# 6coils.net
KiCad netlist of a schematic drawn in EasyEDA
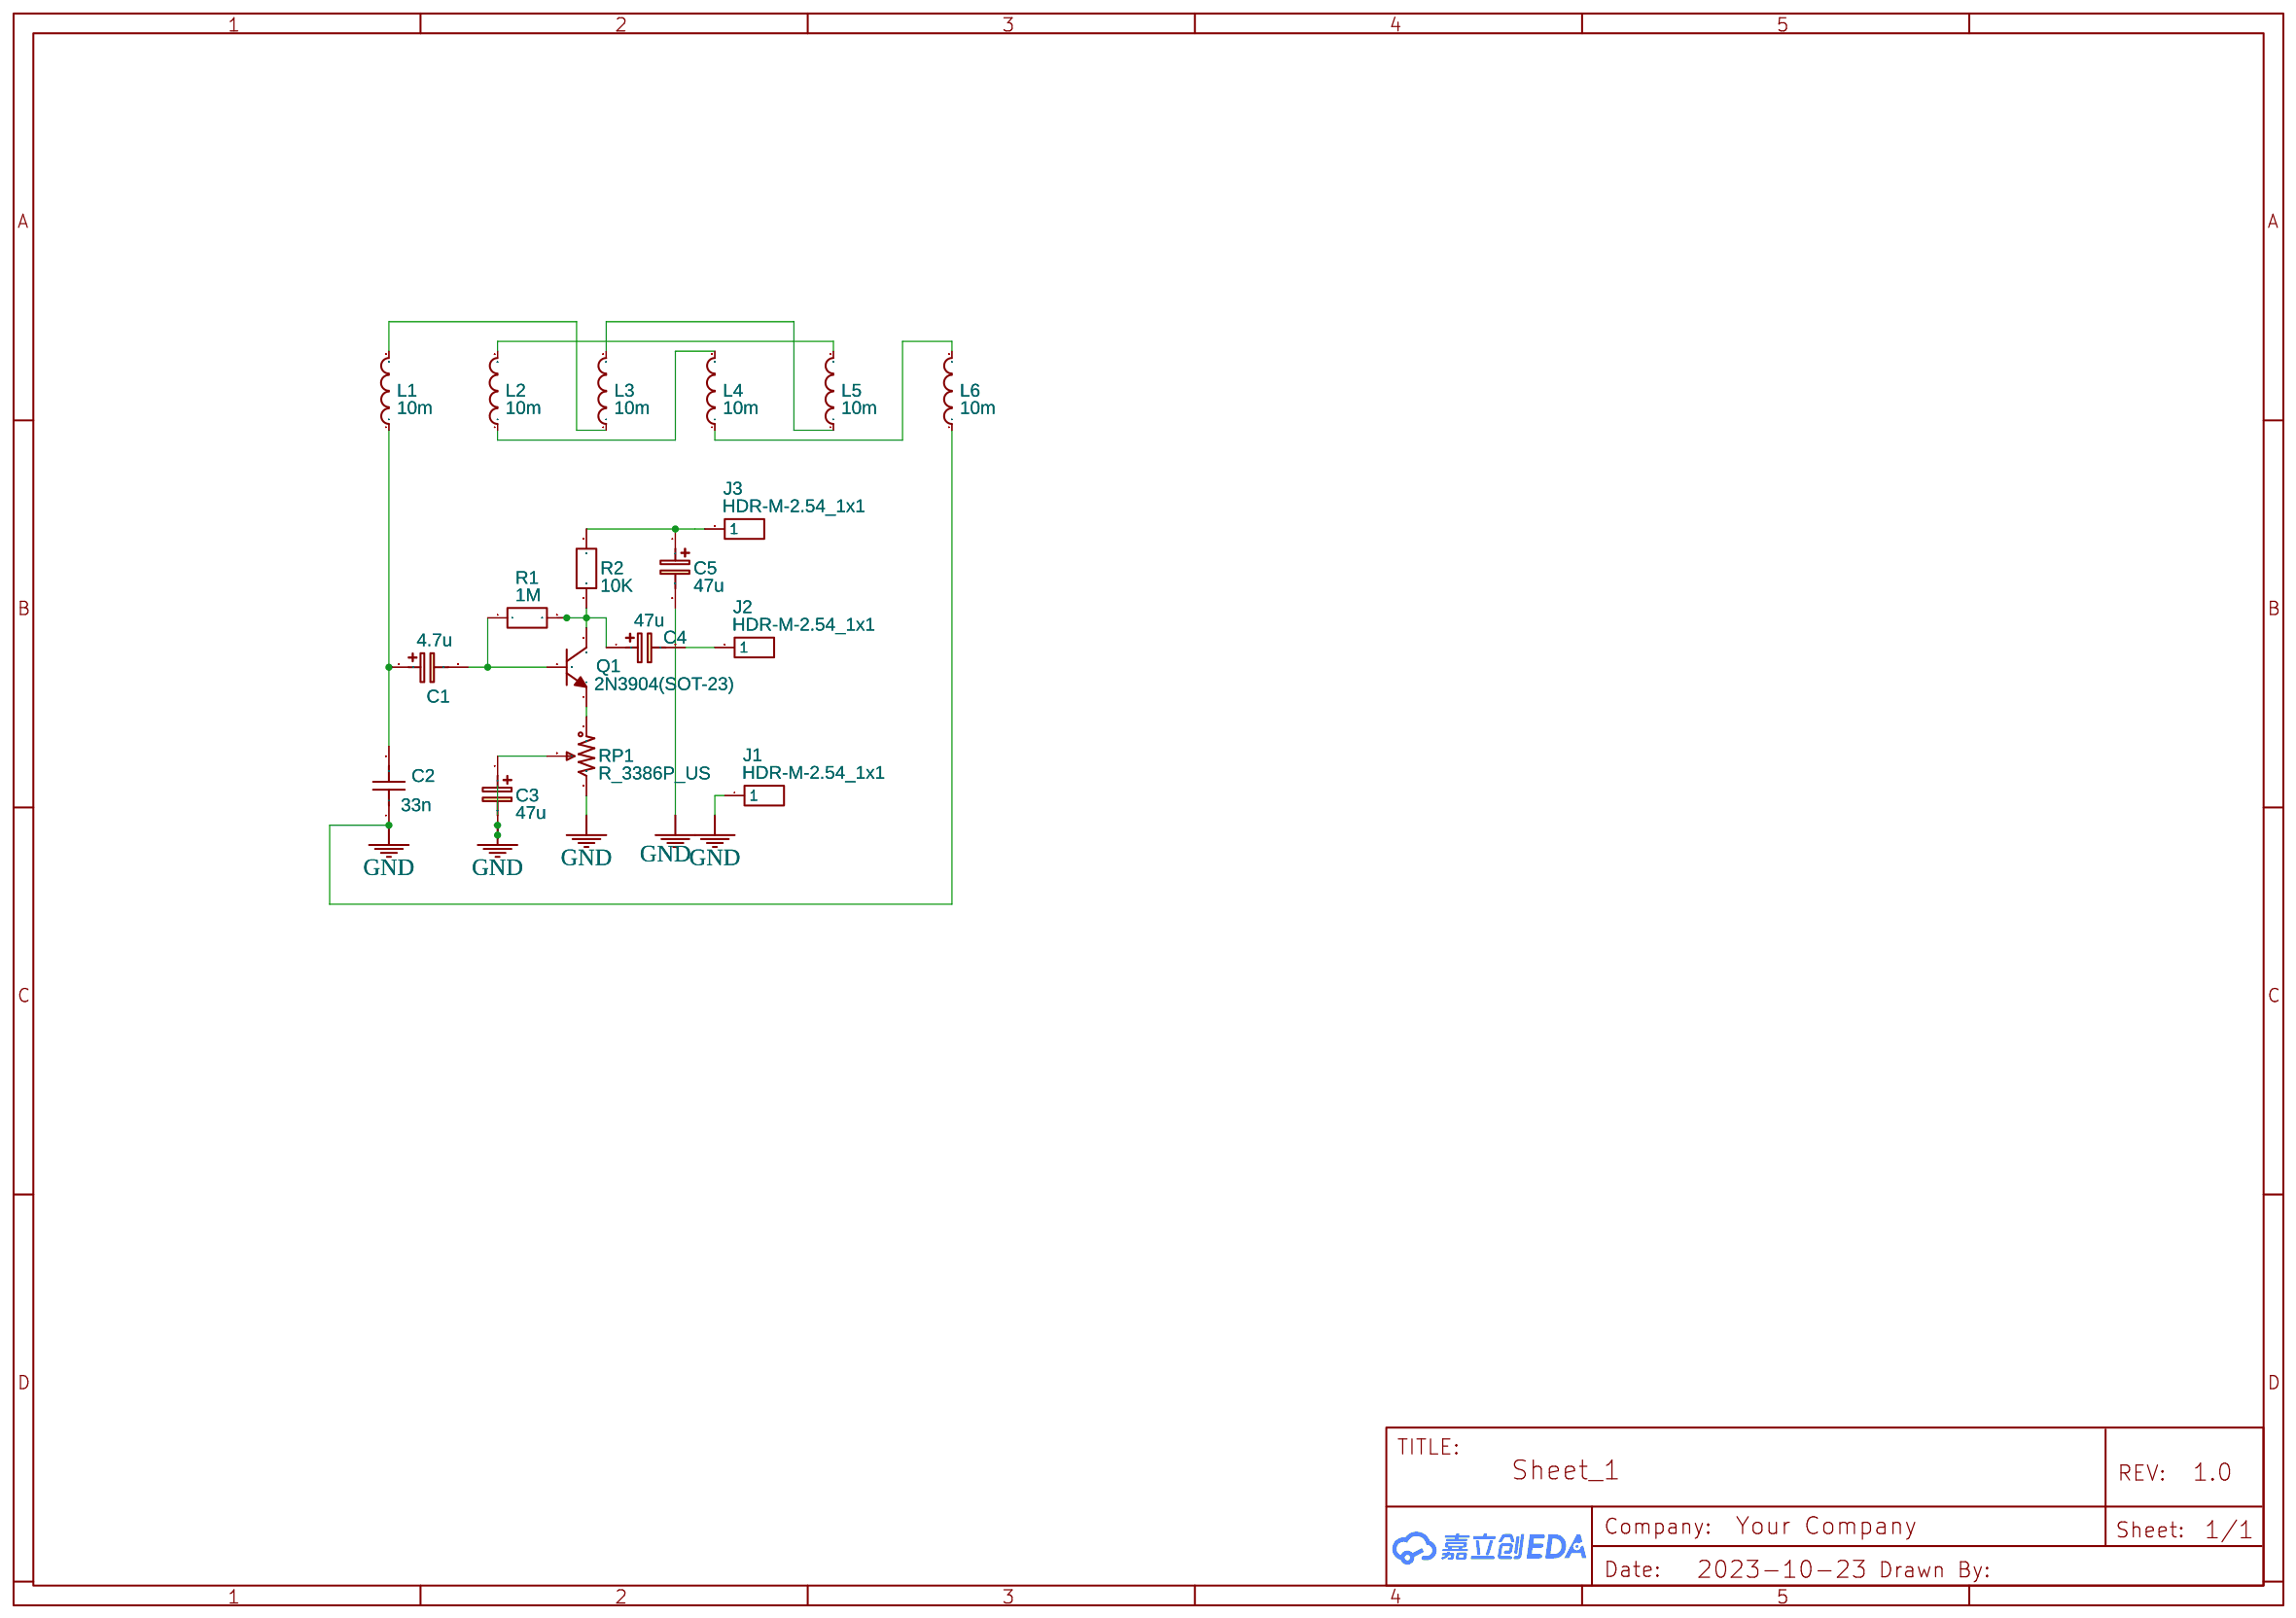
[diagram p0: schematic sheet]

(export (version "E")
  (design (tool "Eeschema 10.0.6"))
  (components
    (comp (ref "C1") (value "4.7u") (libsource (lib "") (part "C_Tan_SMD_A_EU_2")))
    (comp (ref "C2") (value "33n") (libsource (lib "") (part "C_0603_US")))
    (comp (ref "C3") (value "47u") (libsource (lib "") (part "C_Tan_SMD_A_EU")))
    (comp (ref "C4") (value "47u") (libsource (lib "") (part "C_Tan_SMD_A_EU_1")))
    (comp (ref "C5") (value "47u") (libsource (lib "") (part "C_Tan_SMD_A_EU_3")))
    (comp (ref "J1")
      (value "HDR-M-2.54_1x1")
      (fields (field (name "BOM_Supplier Part") "C81276"))
      (libsource (lib "") (part "HDR-M-2.54_1x1"))
    )
    (comp (ref "J2")
      (value "HDR-M-2.54_1x1")
      (fields (field (name "BOM_Supplier Part") "C81276"))
      (libsource (lib "") (part "HDR-M-2.54_1x1"))
    )
    (comp (ref "J3")
      (value "HDR-M-2.54_1x1")
      (fields (field (name "BOM_Supplier Part") "C81276"))
      (libsource (lib "") (part "HDR-M-2.54_1x1"))
    )
    (comp (ref "L1") (value "10m") (libsource (lib "") (part "L0603_US")))
    (comp (ref "L2") (value "10m") (libsource (lib "") (part "L0603_US")))
    (comp (ref "L3") (value "10m") (libsource (lib "") (part "L0603_US")))
    (comp (ref "L4") (value "10m") (libsource (lib "") (part "L0603_US")))
    (comp (ref "L5") (value "10m") (libsource (lib "") (part "L0603_US")))
    (comp (ref "L6") (value "10m") (libsource (lib "") (part "L0603_US")))
    (comp (ref "Q1")
      (value "2N3904(SOT-23)")
      (fields
        (field (name "BOM_Manufacturer Part") "2n3904S-RTK/PS")
        (field (name "BOM_Supplier Part") "C18536")
      )
      (libsource (lib "") (part "2N3904(SOT-23)"))
    )
    (comp (ref "R1") (value "1M") (libsource (lib "") (part "R_0603_EU")))
    (comp (ref "R2") (value "10K") (libsource (lib "") (part "R_0603_EU_1")))
    (comp (ref "RP1") (value "R_3386P_US") (libsource (lib "") (part "R_3386P_US")))
  )
  (nets
    (net (code "1") (name "GND") (class "Default")
      (node (ref "C2") (pin "1") (pinfunction "1_1") (pintype "unspecified"))
      (node (ref "C3") (pin "2") (pinfunction "2_2") (pintype "unspecified"))
      (node (ref "C5") (pin "2") (pinfunction "2_2") (pintype "unspecified"))
      (node (ref "J1") (pin "1") (pinfunction "1_1") (pintype "input"))
      (node (ref "L6") (pin "1") (pinfunction "1_1") (pintype "unspecified"))
      (node (ref "RP1") (pin "3") (pinfunction "3_3") (pintype "unspecified"))
    )
    (net (code "2") (name "Net-(C1-Pad1)") (class "Default")
      (node (ref "C1") (pin "1") (pinfunction "1_1") (pintype "unspecified"))
      (node (ref "C2") (pin "2") (pinfunction "2_2") (pintype "unspecified"))
      (node (ref "L1") (pin "1") (pinfunction "1_1") (pintype "unspecified"))
    )
    (net (code "3") (name "Net-(C3-Pad1)") (class "Default")
      (node (ref "C3") (pin "1") (pinfunction "1_1") (pintype "unspecified"))
      (node (ref "RP1") (pin "2") (pinfunction "2_2") (pintype "unspecified"))
    )
    (net (code "4") (name "Net-(C4-Pad2)") (class "Default")
      (node (ref "C4") (pin "2") (pinfunction "2_2") (pintype "unspecified"))
      (node (ref "J2") (pin "1") (pinfunction "1_1") (pintype "input"))
    )
    (net (code "5") (name "Net-(C5-Pad1)") (class "Default")
      (node (ref "C5") (pin "1") (pinfunction "1_1") (pintype "unspecified"))
      (node (ref "J3") (pin "1") (pinfunction "1_1") (pintype "input"))
      (node (ref "R2") (pin "2") (pinfunction "2_2") (pintype "unspecified"))
    )
    (net (code "6") (name "Net-(L1-Pad2)") (class "Default")
      (node (ref "L1") (pin "2") (pinfunction "2_2") (pintype "unspecified"))
      (node (ref "L3") (pin "1") (pinfunction "1_1") (pintype "unspecified"))
    )
    (net (code "7") (name "Net-(L2-Pad1)") (class "Default")
      (node (ref "L2") (pin "1") (pinfunction "1_1") (pintype "unspecified"))
      (node (ref "L4") (pin "2") (pinfunction "2_2") (pintype "unspecified"))
    )
    (net (code "8") (name "Net-(L2-Pad2)") (class "Default")
      (node (ref "L2") (pin "2") (pinfunction "2_2") (pintype "unspecified"))
      (node (ref "L5") (pin "2") (pinfunction "2_2") (pintype "unspecified"))
    )
    (net (code "9") (name "Net-(L3-Pad2)") (class "Default")
      (node (ref "L3") (pin "2") (pinfunction "2_2") (pintype "unspecified"))
      (node (ref "L5") (pin "1") (pinfunction "1_1") (pintype "unspecified"))
    )
    (net (code "10") (name "Net-(L4-Pad1)") (class "Default")
      (node (ref "L4") (pin "1") (pinfunction "1_1") (pintype "unspecified"))
      (node (ref "L6") (pin "2") (pinfunction "2_2") (pintype "unspecified"))
    )
    (net (code "11") (name "Net-(Q1-B)") (class "Default")
      (node (ref "C1") (pin "2") (pinfunction "2_2") (pintype "unspecified"))
      (node (ref "Q1") (pin "2") (pinfunction "B_2") (pintype "input"))
      (node (ref "R1") (pin "1") (pinfunction "1_1") (pintype "unspecified"))
    )
    (net (code "12") (name "Net-(Q1-C)") (class "Default")
      (node (ref "C4") (pin "1") (pinfunction "1_1") (pintype "unspecified"))
      (node (ref "Q1") (pin "3") (pinfunction "C_3") (pintype "input"))
      (node (ref "R1") (pin "2") (pinfunction "2_2") (pintype "unspecified"))
      (node (ref "R2") (pin "1") (pinfunction "1_1") (pintype "unspecified"))
    )
    (net (code "13") (name "Net-(Q1-E)") (class "Default")
      (node (ref "Q1") (pin "1") (pinfunction "E_1") (pintype "input"))
      (node (ref "RP1") (pin "1") (pinfunction "1_1") (pintype "unspecified"))
    )
  )
)
